# RPiProject.net
KiCad netlist of a schematic drawn in EAGLE
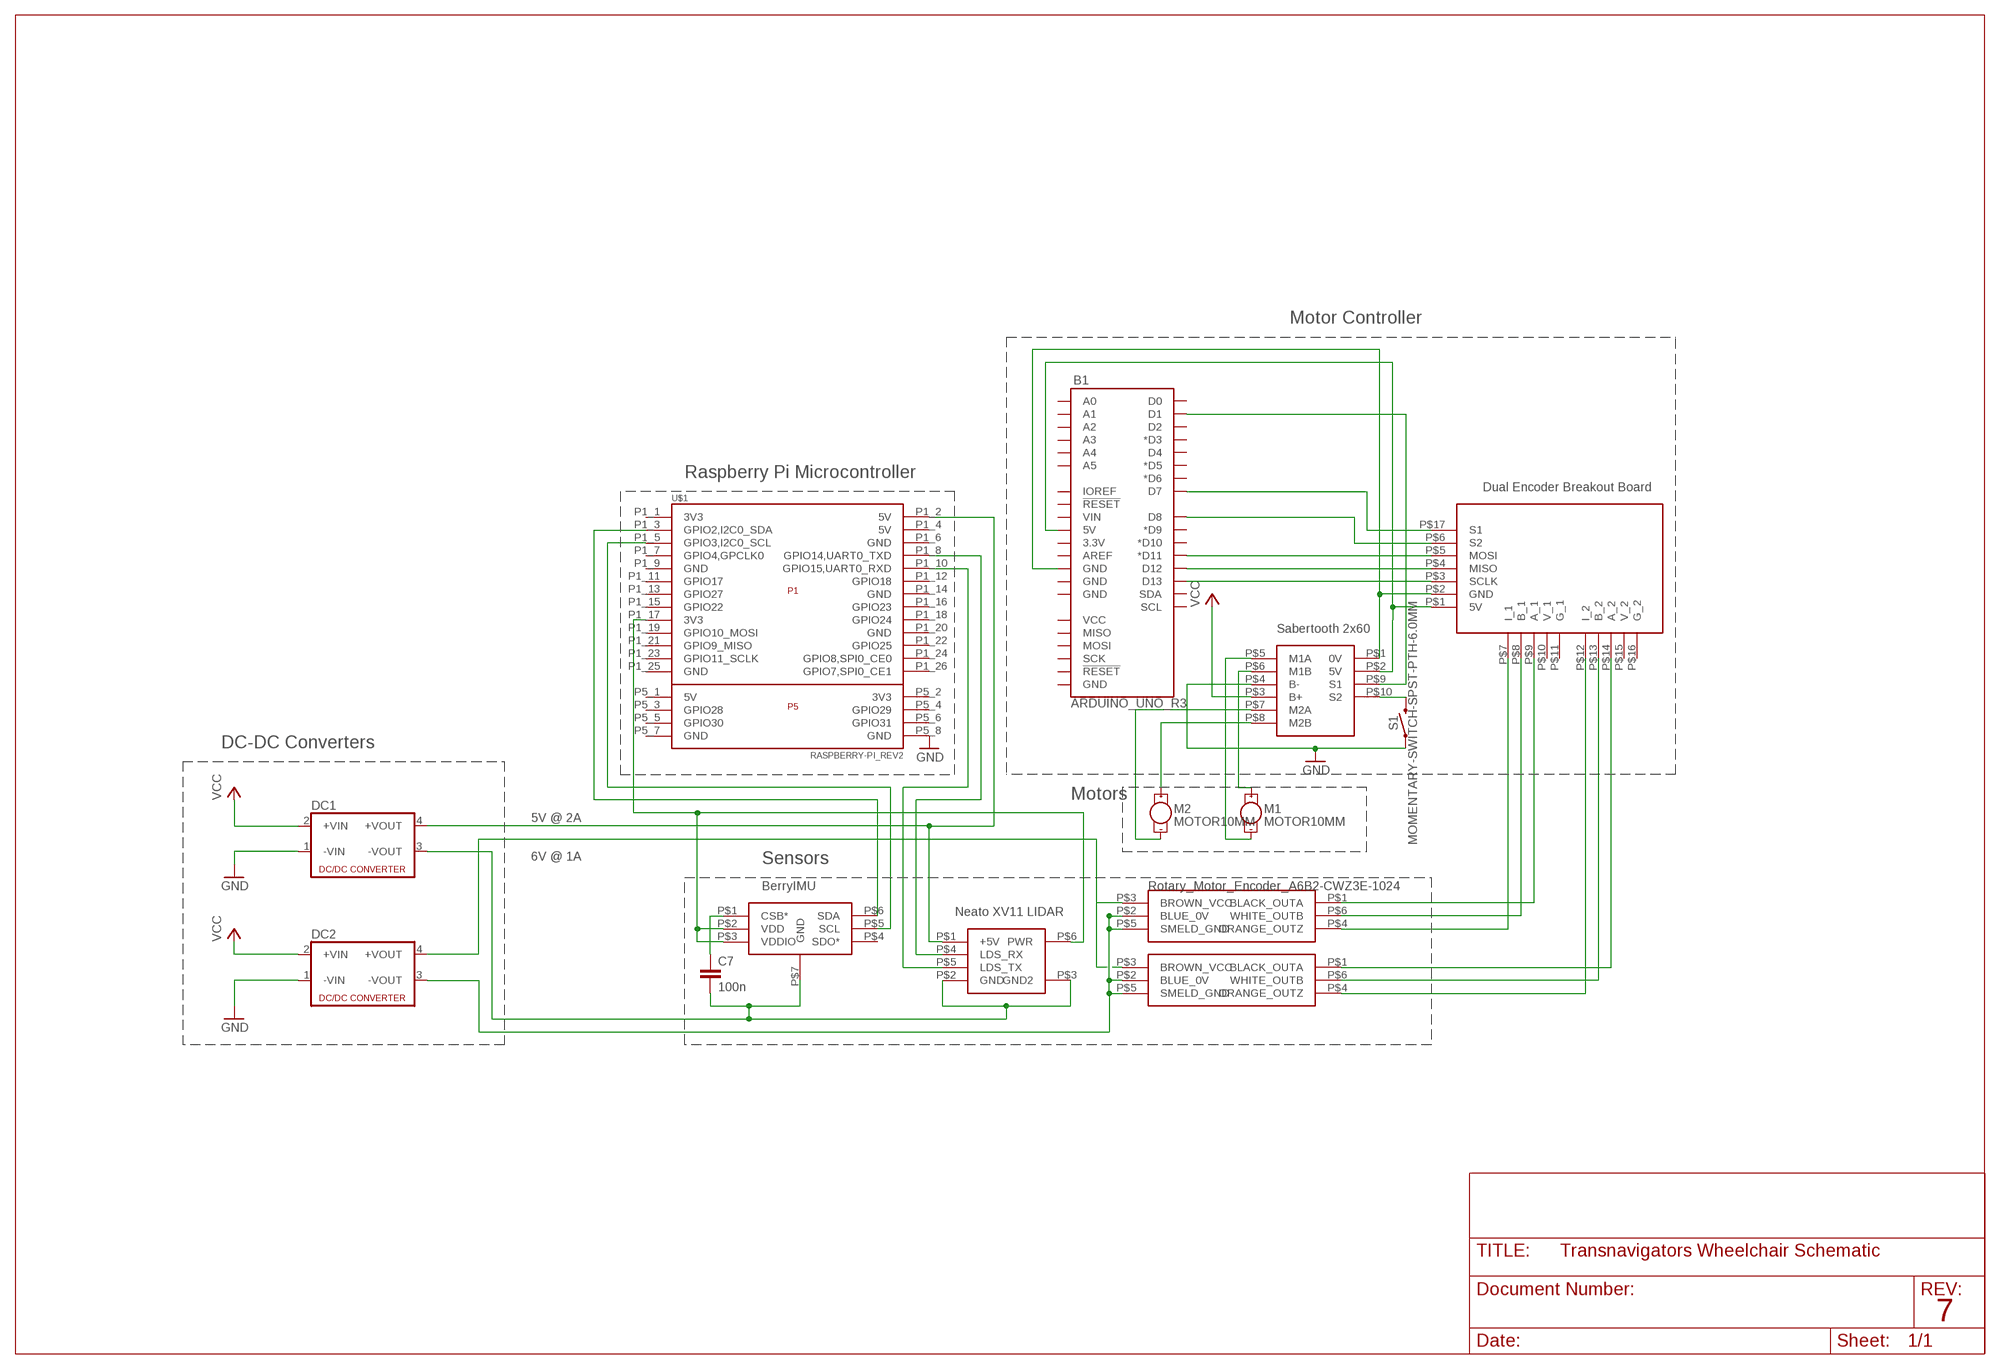
[diagram p0: schematic, sheet 1]

(export (version "E")
  (design (tool "Eeschema 10.0.6"))
  (components
    (comp (ref "B1")
      (value "ARDUINO_UNO_R3")
      (footprint "eagle-import:ARDUINO_R3")
      (libsource (lib "eagle-import") (part "ARDUINO_UNO_R3"))
    )
    (comp (ref "C7")
      (value "100n")
      (footprint "eagle-import:C025-030X050")
      (libsource (lib "eagle-import") (part "C2.5P"))
    )
    (comp (ref "DC1")
      (value "NME")
      (footprint "eagle-import:NME")
      (fields (field (name "MF") "C & D TECHNOLOGIES, INC") (field (name "MPN") "NME1205D"))
      (libsource (lib "eagle-import") (part "NME"))
    )
    (comp (ref "DC2")
      (value "NME")
      (footprint "eagle-import:NME")
      (fields (field (name "MF") "C & D TECHNOLOGIES, INC") (field (name "MPN") "NME1205D"))
      (libsource (lib "eagle-import") (part "NME"))
    )
    (comp (ref "M1")
      (value "MOTOR10MM")
      (footprint "eagle-import:VIBE-MOTOR-10MM")
      (libsource (lib "eagle-import") (part "MOTOR10MM"))
    )
    (comp (ref "M2")
      (value "MOTOR10MM")
      (footprint "eagle-import:VIBE-MOTOR-10MM")
      (libsource (lib "eagle-import") (part "MOTOR10MM"))
    )
    (comp (ref "S1")
      (value "MOMENTARY-SWITCH-SPST-PTH-6.0MM")
      (footprint "eagle-import:TACTILE_SWITCH_PTH_6.0MM")
      (libsource (lib "eagle-import") (part "MOMENTARY-SWITCH-SPST-PTH-6.0MM"))
    )
    (comp (ref "U$1")
      (value "RASPBERRY-PI_REV2")
      (footprint "eagle-import:RASPBERRY-PI_REV2")
      (libsource (lib "eagle-import") (part "RASPBERRY-PI_REV2"))
    )
    (comp (ref "U$2")
      (value "ENCODER_A6B2")
      (footprint "eagle-import:ENCODER_A6B2")
      (libsource (lib "eagle-import") (part "ENCODER_A6B2"))
    )
    (comp (ref "U$3")
      (value "ENCODER_A6B2")
      (footprint "eagle-import:ENCODER_A6B2")
      (libsource (lib "eagle-import") (part "ENCODER_A6B2"))
    )
    (comp (ref "U$4")
      (value "BERRYIMU")
      (footprint "eagle-import:BERRYIMU")
      (libsource (lib "eagle-import") (part "BERRYIMU"))
    )
    (comp (ref "U$5")
      (value "DUAL_LS7366R")
      (footprint "eagle-import:DUAL_LS7366R")
      (libsource (lib "eagle-import") (part "DUAL_LS7366R"))
    )
    (comp (ref "U$6")
      (value "SABERTOOTH2X60")
      (footprint "eagle-import:SABERTOOTH2X60")
      (libsource (lib "eagle-import") (part "SABERTOOTH2X60"))
    )
    (comp (ref "XV11LIDAR")
      (value "XV11LIDAR")
      (footprint "eagle-import:LIDAR")
      (libsource (lib "eagle-import") (part "XV11LIDAR"))
    )
  )
  (nets
    (net (code "1") (name "GND") (class "Default")
      (node (ref "DC1") (pin "1") (pinfunction "-VIN_1") (pintype "passive"))
      (node (ref "DC2") (pin "1") (pinfunction "-VIN_1") (pintype "passive"))
      (node (ref "S1") (pin "1") (pinfunction "1_1") (pintype "passive"))
      (node (ref "U$1") (pin "P5_8") (pinfunction "GND_P5_8") (pintype "bidirectional"))
      (node (ref "U$6") (pin "P$4") (pinfunction "B-_P$4") (pintype "bidirectional"))
    )
    (net (code "2") (name "Net-(B1-*D11)") (class "Default")
      (node (ref "B1") (pin "D11") (pinfunction "*D11_D11") (pintype "bidirectional"))
      (node (ref "U$5") (pin "P$5") (pinfunction "MOSI_P$5") (pintype "bidirectional"))
    )
    (net (code "3") (name "Net-(DC1-+VOUT)") (class "Default")
      (node (ref "DC1") (pin "4") (pinfunction "+VOUT_4") (pintype "passive"))
      (node (ref "U$1") (pin "P1_2") (pinfunction "5V_P1_2") (pintype "bidirectional"))
      (node (ref "XV11LIDAR") (pin "P$1") (pinfunction "+5V_P$1") (pintype "bidirectional"))
    )
    (net (code "4") (name "Net-(DC1--VOUT)") (class "Default")
      (node (ref "C7") (pin "2") (pinfunction "2_2") (pintype "passive"))
      (node (ref "DC1") (pin "3") (pinfunction "-VOUT_3") (pintype "passive"))
      (node (ref "U$4") (pin "P$7") (pinfunction "GND_P$7") (pintype "bidirectional"))
      (node (ref "XV11LIDAR") (pin "P$2") (pinfunction "GND_P$2") (pintype "bidirectional"))
      (node (ref "XV11LIDAR") (pin "P$3") (pinfunction "GND2_P$3") (pintype "bidirectional"))
    )
    (net (code "5") (name "Net-(DC2-+VOUT)") (class "Default")
      (node (ref "DC2") (pin "4") (pinfunction "+VOUT_4") (pintype "passive"))
      (node (ref "U$3") (pin "P$3") (pinfunction "BROWN_VCC_P$3") (pintype "bidirectional"))
    )
    (net (code "6") (name "Net-(DC2--VOUT)") (class "Default")
      (node (ref "DC2") (pin "3") (pinfunction "-VOUT_3") (pintype "passive"))
      (node (ref "U$2") (pin "P$2") (pinfunction "BLUE_0V_P$2") (pintype "bidirectional"))
      (node (ref "U$2") (pin "P$5") (pinfunction "SMELD_GND_P$5") (pintype "bidirectional"))
      (node (ref "U$3") (pin "P$2") (pinfunction "BLUE_0V_P$2") (pintype "bidirectional"))
      (node (ref "U$3") (pin "P$5") (pinfunction "SMELD_GND_P$5") (pintype "bidirectional"))
    )
    (net (code "7") (name "Net-(S1-2)") (class "Default")
      (node (ref "S1") (pin "3") (pinfunction "2_3") (pintype "passive"))
      (node (ref "U$6") (pin "P$10") (pinfunction "S2_P$10") (pintype "bidirectional"))
    )
    (net (code "8") (name "Net-(U$1-GPIO2,I2C0_SDA)") (class "Default")
      (node (ref "U$1") (pin "P1_3") (pinfunction "GPIO2,I2C0_SDA_P1_3") (pintype "bidirectional"))
      (node (ref "U$4") (pin "P$6") (pinfunction "SDA_P$6") (pintype "bidirectional"))
    )
    (net (code "9") (name "Net-(U$1-GPIO3,I2C0_SCL)") (class "Default")
      (node (ref "U$1") (pin "P1_5") (pinfunction "GPIO3,I2C0_SCL_P1_5") (pintype "bidirectional"))
      (node (ref "U$4") (pin "P$5") (pinfunction "SCL_P$5") (pintype "bidirectional"))
    )
    (net (code "10") (name "Net-(U$1-GPIO14,UART0_TXD)") (class "Default")
      (node (ref "U$1") (pin "P1_8") (pinfunction "GPIO14,UART0_TXD_P1_8") (pintype "bidirectional"))
      (node (ref "XV11LIDAR") (pin "P$4") (pinfunction "LDS_RX_P$4") (pintype "bidirectional"))
    )
    (net (code "11") (name "Net-(U$1-GPIO15,UART0_RXD)") (class "Default")
      (node (ref "U$1") (pin "P1_10") (pinfunction "GPIO15,UART0_RXD_P1_10") (pintype "bidirectional"))
      (node (ref "XV11LIDAR") (pin "P$5") (pinfunction "LDS_TX_P$5") (pintype "bidirectional"))
    )
    (net (code "12") (name "Net-(U$2-BLACK_OUTA)") (class "Default")
      (node (ref "U$2") (pin "P$1") (pinfunction "BLACK_OUTA_P$1") (pintype "bidirectional"))
      (node (ref "U$5") (pin "P$9") (pinfunction "A_1_P$9") (pintype "bidirectional"))
    )
    (net (code "13") (name "Net-(U$2-ORANGE_OUTZ)") (class "Default")
      (node (ref "U$2") (pin "P$4") (pinfunction "ORANGE_OUTZ_P$4") (pintype "bidirectional"))
      (node (ref "U$5") (pin "P$7") (pinfunction "I_1_P$7") (pintype "bidirectional"))
    )
    (net (code "14") (name "Net-(U$2-WHITE_OUTB)") (class "Default")
      (node (ref "U$2") (pin "P$6") (pinfunction "WHITE_OUTB_P$6") (pintype "bidirectional"))
      (node (ref "U$5") (pin "P$8") (pinfunction "B_1_P$8") (pintype "bidirectional"))
    )
    (net (code "15") (name "Net-(U$3-BLACK_OUTA)") (class "Default")
      (node (ref "U$3") (pin "P$1") (pinfunction "BLACK_OUTA_P$1") (pintype "bidirectional"))
      (node (ref "U$5") (pin "P$14") (pinfunction "A_2_P$14") (pintype "bidirectional"))
    )
    (net (code "16") (name "Net-(U$3-ORANGE_OUTZ)") (class "Default")
      (node (ref "U$3") (pin "P$4") (pinfunction "ORANGE_OUTZ_P$4") (pintype "bidirectional"))
      (node (ref "U$5") (pin "P$12") (pinfunction "I_2_P$12") (pintype "bidirectional"))
    )
    (net (code "17") (name "Net-(U$3-WHITE_OUTB)") (class "Default")
      (node (ref "U$3") (pin "P$6") (pinfunction "WHITE_OUTB_P$6") (pintype "bidirectional"))
      (node (ref "U$5") (pin "P$13") (pinfunction "B_2_P$13") (pintype "bidirectional"))
    )
    (net (code "18") (name "Net-(U$4-CSB*)") (class "Default")
      (node (ref "C7") (pin "1") (pinfunction "1_1") (pintype "passive"))
      (node (ref "U$4") (pin "P$1") (pinfunction "CSB*_P$1") (pintype "bidirectional"))
    )
    (net (code "19") (name "Net-(U$4-VDD)") (class "Default")
      (node (ref "U$1") (pin "P1_17") (pinfunction "3V3_P1_17") (pintype "bidirectional"))
      (node (ref "U$4") (pin "P$2") (pinfunction "VDD_P$2") (pintype "bidirectional"))
      (node (ref "U$4") (pin "P$3") (pinfunction "VDDIO_P$3") (pintype "bidirectional"))
      (node (ref "XV11LIDAR") (pin "P$6") (pinfunction "PWR_P$6") (pintype "bidirectional"))
    )
    (net (code "20") (name "Net-(U$5-5V)") (class "Default")
      (node (ref "B1") (pin "5V") (pinfunction "5V_5V") (pintype "bidirectional"))
      (node (ref "U$5") (pin "P$1") (pinfunction "5V_P$1") (pintype "bidirectional"))
      (node (ref "U$6") (pin "P$2") (pinfunction "5V_P$2") (pintype "bidirectional"))
    )
    (net (code "21") (name "Net-(U$5-GND)") (class "Default")
      (node (ref "B1") (pin "GND@4") (pinfunction "GND_GND@4") (pintype "bidirectional"))
      (node (ref "U$5") (pin "P$2") (pinfunction "GND_P$2") (pintype "bidirectional"))
      (node (ref "U$6") (pin "P$1") (pinfunction "0V_P$1") (pintype "bidirectional"))
    )
    (net (code "22") (name "Net-(U$5-MISO)") (class "Default")
      (node (ref "B1") (pin "D12") (pinfunction "D12_D12") (pintype "bidirectional"))
      (node (ref "U$5") (pin "P$4") (pinfunction "MISO_P$4") (pintype "bidirectional"))
    )
    (net (code "23") (name "Net-(U$5-S1)") (class "Default")
      (node (ref "B1") (pin "D7") (pinfunction "D7_D7") (pintype "bidirectional"))
      (node (ref "U$5") (pin "P$17") (pinfunction "S1_P$17") (pintype "bidirectional"))
    )
    (net (code "24") (name "Net-(U$5-S2)") (class "Default")
      (node (ref "B1") (pin "D8") (pinfunction "D8_D8") (pintype "bidirectional"))
      (node (ref "U$5") (pin "P$6") (pinfunction "S2_P$6") (pintype "bidirectional"))
    )
    (net (code "25") (name "Net-(U$5-SCLK)") (class "Default")
      (node (ref "B1") (pin "D13") (pinfunction "D13_D13") (pintype "bidirectional"))
      (node (ref "U$5") (pin "P$3") (pinfunction "SCLK_P$3") (pintype "bidirectional"))
    )
    (net (code "26") (name "Net-(U$6-M1A)") (class "Default")
      (node (ref "M1") (pin "-") (pinfunction "-_-") (pintype "bidirectional"))
      (node (ref "U$6") (pin "P$5") (pinfunction "M1A_P$5") (pintype "bidirectional"))
    )
    (net (code "27") (name "Net-(U$6-M1B)") (class "Default")
      (node (ref "M1") (pin "+") (pinfunction "+_+") (pintype "bidirectional"))
      (node (ref "U$6") (pin "P$6") (pinfunction "M1B_P$6") (pintype "bidirectional"))
    )
    (net (code "28") (name "Net-(U$6-M2A)") (class "Default")
      (node (ref "M2") (pin "-") (pinfunction "-_-") (pintype "bidirectional"))
      (node (ref "U$6") (pin "P$7") (pinfunction "M2A_P$7") (pintype "bidirectional"))
    )
    (net (code "29") (name "Net-(U$6-M2B)") (class "Default")
      (node (ref "M2") (pin "+") (pinfunction "+_+") (pintype "bidirectional"))
      (node (ref "U$6") (pin "P$8") (pinfunction "M2B_P$8") (pintype "bidirectional"))
    )
    (net (code "30") (name "Net-(U$6-S1)") (class "Default")
      (node (ref "B1") (pin "D1") (pinfunction "D1_D1") (pintype "bidirectional"))
      (node (ref "U$6") (pin "P$9") (pinfunction "S1_P$9") (pintype "bidirectional"))
    )
    (net (code "31") (name "VCC") (class "Default")
      (node (ref "DC1") (pin "2") (pinfunction "+VIN_2") (pintype "passive"))
      (node (ref "DC2") (pin "2") (pinfunction "+VIN_2") (pintype "passive"))
      (node (ref "U$6") (pin "P$3") (pinfunction "B+_P$3") (pintype "bidirectional"))
    )
    (net (code "32") (name "unconnected-(B1-*D3-PadD3)") (class "Default")
      (node (ref "B1") (pin "D3") (pinfunction "*D3_D3") (pintype "bidirectional"))
    )
    (net (code "33") (name "unconnected-(B1-*D5-PadD5)") (class "Default")
      (node (ref "B1") (pin "D5") (pinfunction "*D5_D5") (pintype "bidirectional"))
    )
    (net (code "34") (name "unconnected-(B1-*D6-PadD6)") (class "Default")
      (node (ref "B1") (pin "D6") (pinfunction "*D6_D6") (pintype "bidirectional"))
    )
    (net (code "35") (name "unconnected-(B1-*D9-PadD9)") (class "Default")
      (node (ref "B1") (pin "D9") (pinfunction "*D9_D9") (pintype "bidirectional"))
    )
    (net (code "36") (name "unconnected-(B1-*D10-PadD10)") (class "Default")
      (node (ref "B1") (pin "D10") (pinfunction "*D10_D10") (pintype "bidirectional"))
    )
    (net (code "37") (name "unconnected-(B1-GND-PadGND@1)") (class "Default")
      (node (ref "B1") (pin "GND@1") (pinfunction "GND_GND@1") (pintype "bidirectional"))
    )
    (net (code "38") (name "unconnected-(B1-GND-PadGND@2)") (class "Default")
      (node (ref "B1") (pin "GND@2") (pinfunction "GND_GND@2") (pintype "bidirectional"))
    )
    (net (code "39") (name "unconnected-(B1-GND-PadGND@3)") (class "Default")
      (node (ref "B1") (pin "GND@3") (pinfunction "GND_GND@3") (pintype "bidirectional"))
    )
    (net (code "40") (name "unconnected-(B1-Pad3.3V)") (class "Default")
      (node (ref "B1") (pin "3.3V") (pinfunction "3.3V_3.3V") (pintype "bidirectional"))
    )
    (net (code "41") (name "unconnected-(B1-PadA0)") (class "Default")
      (node (ref "B1") (pin "A0") (pinfunction "A0_A0") (pintype "bidirectional"))
    )
    (net (code "42") (name "unconnected-(B1-PadA1)") (class "Default")
      (node (ref "B1") (pin "A1") (pinfunction "A1_A1") (pintype "bidirectional"))
    )
    (net (code "43") (name "unconnected-(B1-PadA2)") (class "Default")
      (node (ref "B1") (pin "A2") (pinfunction "A2_A2") (pintype "bidirectional"))
    )
    (net (code "44") (name "unconnected-(B1-PadA3)") (class "Default")
      (node (ref "B1") (pin "A3") (pinfunction "A3_A3") (pintype "bidirectional"))
    )
    (net (code "45") (name "unconnected-(B1-PadA4)") (class "Default")
      (node (ref "B1") (pin "A4") (pinfunction "A4_A4") (pintype "bidirectional"))
    )
    (net (code "46") (name "unconnected-(B1-PadA5)") (class "Default")
      (node (ref "B1") (pin "A5") (pinfunction "A5_A5") (pintype "bidirectional"))
    )
    (net (code "47") (name "unconnected-(B1-PadAREF)") (class "Default")
      (node (ref "B1") (pin "AREF") (pinfunction "AREF_AREF") (pintype "bidirectional"))
    )
    (net (code "48") (name "unconnected-(B1-PadD0)") (class "Default")
      (node (ref "B1") (pin "D0") (pinfunction "D0_D0") (pintype "bidirectional"))
    )
    (net (code "49") (name "unconnected-(B1-PadD2)") (class "Default")
      (node (ref "B1") (pin "D2") (pinfunction "D2_D2") (pintype "bidirectional"))
    )
    (net (code "50") (name "unconnected-(B1-PadD4)") (class "Default")
      (node (ref "B1") (pin "D4") (pinfunction "D4_D4") (pintype "bidirectional"))
    )
    (net (code "51") (name "unconnected-(B1-PadIOREF)") (class "Default")
      (node (ref "B1") (pin "IOREF") (pinfunction "IOREF_IOREF") (pintype "bidirectional"))
    )
    (net (code "52") (name "unconnected-(B1-PadMISO)") (class "Default")
      (node (ref "B1") (pin "MISO") (pinfunction "MISO_MISO") (pintype "bidirectional"))
    )
    (net (code "53") (name "unconnected-(B1-PadMOSI)") (class "Default")
      (node (ref "B1") (pin "MOSI") (pinfunction "MOSI_MOSI") (pintype "bidirectional"))
    )
    (net (code "54") (name "unconnected-(B1-PadSCK)") (class "Default")
      (node (ref "B1") (pin "SCK") (pinfunction "SCK_SCK") (pintype "bidirectional"))
    )
    (net (code "55") (name "unconnected-(B1-PadSCL)") (class "Default")
      (node (ref "B1") (pin "SCL") (pinfunction "SCL_SCL") (pintype "bidirectional"))
    )
    (net (code "56") (name "unconnected-(B1-PadSDA)") (class "Default")
      (node (ref "B1") (pin "SDA") (pinfunction "SDA_SDA") (pintype "bidirectional"))
    )
    (net (code "57") (name "unconnected-(B1-PadVCC)") (class "Default")
      (node (ref "B1") (pin "VCC") (pinfunction "VCC_VCC") (pintype "bidirectional"))
    )
    (net (code "58") (name "unconnected-(B1-PadVIN)") (class "Default")
      (node (ref "B1") (pin "VIN") (pinfunction "VIN_VIN") (pintype "bidirectional"))
    )
    (net (code "59") (name "unconnected-(B1-~{RESET}-PadRESET@1)") (class "Default")
      (node (ref "B1") (pin "RESET@1") (pinfunction "~{RESET}_RESET@1") (pintype "bidirectional"))
    )
    (net (code "60") (name "unconnected-(B1-~{RESET}-PadRESET@2)") (class "Default")
      (node (ref "B1") (pin "RESET@2") (pinfunction "~{RESET}_RESET@2") (pintype "bidirectional"))
    )
    (net (code "61") (name "unconnected-(U$1-3V3-PadP1_1)") (class "Default")
      (node (ref "U$1") (pin "P1_1") (pinfunction "3V3_P1_1") (pintype "bidirectional"))
    )
    (net (code "62") (name "unconnected-(U$1-3V3-PadP5_2)") (class "Default")
      (node (ref "U$1") (pin "P5_2") (pinfunction "3V3_P5_2") (pintype "bidirectional"))
    )
    (net (code "63") (name "unconnected-(U$1-5V-PadP1_4)") (class "Default")
      (node (ref "U$1") (pin "P1_4") (pinfunction "5V_P1_4") (pintype "bidirectional"))
    )
    (net (code "64") (name "unconnected-(U$1-5V-PadP5_1)") (class "Default")
      (node (ref "U$1") (pin "P5_1") (pinfunction "5V_P5_1") (pintype "bidirectional"))
    )
    (net (code "65") (name "unconnected-(U$1-GND-PadP1_6)") (class "Default")
      (node (ref "U$1") (pin "P1_6") (pinfunction "GND_P1_6") (pintype "bidirectional"))
    )
    (net (code "66") (name "unconnected-(U$1-GND-PadP1_9)") (class "Default")
      (node (ref "U$1") (pin "P1_9") (pinfunction "GND_P1_9") (pintype "bidirectional"))
    )
    (net (code "67") (name "unconnected-(U$1-GND-PadP1_14)") (class "Default")
      (node (ref "U$1") (pin "P1_14") (pinfunction "GND_P1_14") (pintype "bidirectional"))
    )
    (net (code "68") (name "unconnected-(U$1-GND-PadP1_20)") (class "Default")
      (node (ref "U$1") (pin "P1_20") (pinfunction "GND_P1_20") (pintype "bidirectional"))
    )
    (net (code "69") (name "unconnected-(U$1-GND-PadP1_25)") (class "Default")
      (node (ref "U$1") (pin "P1_25") (pinfunction "GND_P1_25") (pintype "bidirectional"))
    )
    (net (code "70") (name "unconnected-(U$1-GND-PadP5_7)") (class "Default")
      (node (ref "U$1") (pin "P5_7") (pinfunction "GND_P5_7") (pintype "bidirectional"))
    )
    (net (code "71") (name "unconnected-(U$1-GPIO4,GPCLK0-PadP1_7)") (class "Default")
      (node (ref "U$1") (pin "P1_7") (pinfunction "GPIO4,GPCLK0_P1_7") (pintype "bidirectional"))
    )
    (net (code "72") (name "unconnected-(U$1-GPIO7,SPI0_CE1-PadP1_26)") (class "Default")
      (node (ref "U$1") (pin "P1_26") (pinfunction "GPIO7,SPI0_CE1_P1_26") (pintype "bidirectional"))
    )
    (net (code "73") (name "unconnected-(U$1-GPIO8,SPI0_CE0-PadP1_24)") (class "Default")
      (node (ref "U$1") (pin "P1_24") (pinfunction "GPIO8,SPI0_CE0_P1_24") (pintype "bidirectional"))
    )
    (net (code "74") (name "unconnected-(U$1-GPIO9_MISO-PadP1_21)") (class "Default")
      (node (ref "U$1") (pin "P1_21") (pinfunction "GPIO9_MISO_P1_21") (pintype "bidirectional"))
    )
    (net (code "75") (name "unconnected-(U$1-GPIO10_MOSI-PadP1_19)") (class "Default")
      (node (ref "U$1") (pin "P1_19") (pinfunction "GPIO10_MOSI_P1_19") (pintype "bidirectional"))
    )
    (net (code "76") (name "unconnected-(U$1-GPIO11_SCLK-PadP1_23)") (class "Default")
      (node (ref "U$1") (pin "P1_23") (pinfunction "GPIO11_SCLK_P1_23") (pintype "bidirectional"))
    )
    (net (code "77") (name "unconnected-(U$1-GPIO17-PadP1_11)") (class "Default")
      (node (ref "U$1") (pin "P1_11") (pinfunction "GPIO17_P1_11") (pintype "bidirectional"))
    )
    (net (code "78") (name "unconnected-(U$1-GPIO18-PadP1_12)") (class "Default")
      (node (ref "U$1") (pin "P1_12") (pinfunction "GPIO18_P1_12") (pintype "bidirectional"))
    )
    (net (code "79") (name "unconnected-(U$1-GPIO22-PadP1_15)") (class "Default")
      (node (ref "U$1") (pin "P1_15") (pinfunction "GPIO22_P1_15") (pintype "bidirectional"))
    )
    (net (code "80") (name "unconnected-(U$1-GPIO23-PadP1_16)") (class "Default")
      (node (ref "U$1") (pin "P1_16") (pinfunction "GPIO23_P1_16") (pintype "bidirectional"))
    )
    (net (code "81") (name "unconnected-(U$1-GPIO24-PadP1_18)") (class "Default")
      (node (ref "U$1") (pin "P1_18") (pinfunction "GPIO24_P1_18") (pintype "bidirectional"))
    )
    (net (code "82") (name "unconnected-(U$1-GPIO25-PadP1_22)") (class "Default")
      (node (ref "U$1") (pin "P1_22") (pinfunction "GPIO25_P1_22") (pintype "bidirectional"))
    )
    (net (code "83") (name "unconnected-(U$1-GPIO27-PadP1_13)") (class "Default")
      (node (ref "U$1") (pin "P1_13") (pinfunction "GPIO27_P1_13") (pintype "bidirectional"))
    )
    (net (code "84") (name "unconnected-(U$1-GPIO28-PadP5_3)") (class "Default")
      (node (ref "U$1") (pin "P5_3") (pinfunction "GPIO28_P5_3") (pintype "bidirectional"))
    )
    (net (code "85") (name "unconnected-(U$1-GPIO29-PadP5_4)") (class "Default")
      (node (ref "U$1") (pin "P5_4") (pinfunction "GPIO29_P5_4") (pintype "bidirectional"))
    )
    (net (code "86") (name "unconnected-(U$1-GPIO30-PadP5_5)") (class "Default")
      (node (ref "U$1") (pin "P5_5") (pinfunction "GPIO30_P5_5") (pintype "bidirectional"))
    )
    (net (code "87") (name "unconnected-(U$1-GPIO31-PadP5_6)") (class "Default")
      (node (ref "U$1") (pin "P5_6") (pinfunction "GPIO31_P5_6") (pintype "bidirectional"))
    )
    (net (code "88") (name "unconnected-(U$2-BROWN_VCC-PadP$3)") (class "Default")
      (node (ref "U$2") (pin "P$3") (pinfunction "BROWN_VCC_P$3") (pintype "bidirectional"))
    )
    (net (code "89") (name "unconnected-(U$4-SDO*-PadP$4)") (class "Default")
      (node (ref "U$4") (pin "P$4") (pinfunction "SDO*_P$4") (pintype "bidirectional"))
    )
    (net (code "90") (name "unconnected-(U$5-G_1-PadP$11)") (class "Default")
      (node (ref "U$5") (pin "P$11") (pinfunction "G_1_P$11") (pintype "bidirectional"))
    )
    (net (code "91") (name "unconnected-(U$5-G_2-PadP$16)") (class "Default")
      (node (ref "U$5") (pin "P$16") (pinfunction "G_2_P$16") (pintype "bidirectional"))
    )
    (net (code "92") (name "unconnected-(U$5-V_1-PadP$10)") (class "Default")
      (node (ref "U$5") (pin "P$10") (pinfunction "V_1_P$10") (pintype "bidirectional"))
    )
    (net (code "93") (name "unconnected-(U$5-V_2-PadP$15)") (class "Default")
      (node (ref "U$5") (pin "P$15") (pinfunction "V_2_P$15") (pintype "bidirectional"))
    )
  )
)
